# SCH_SAO-ctf-2024_2024-02-16.net
KiCad netlist of a schematic drawn in EasyEDA
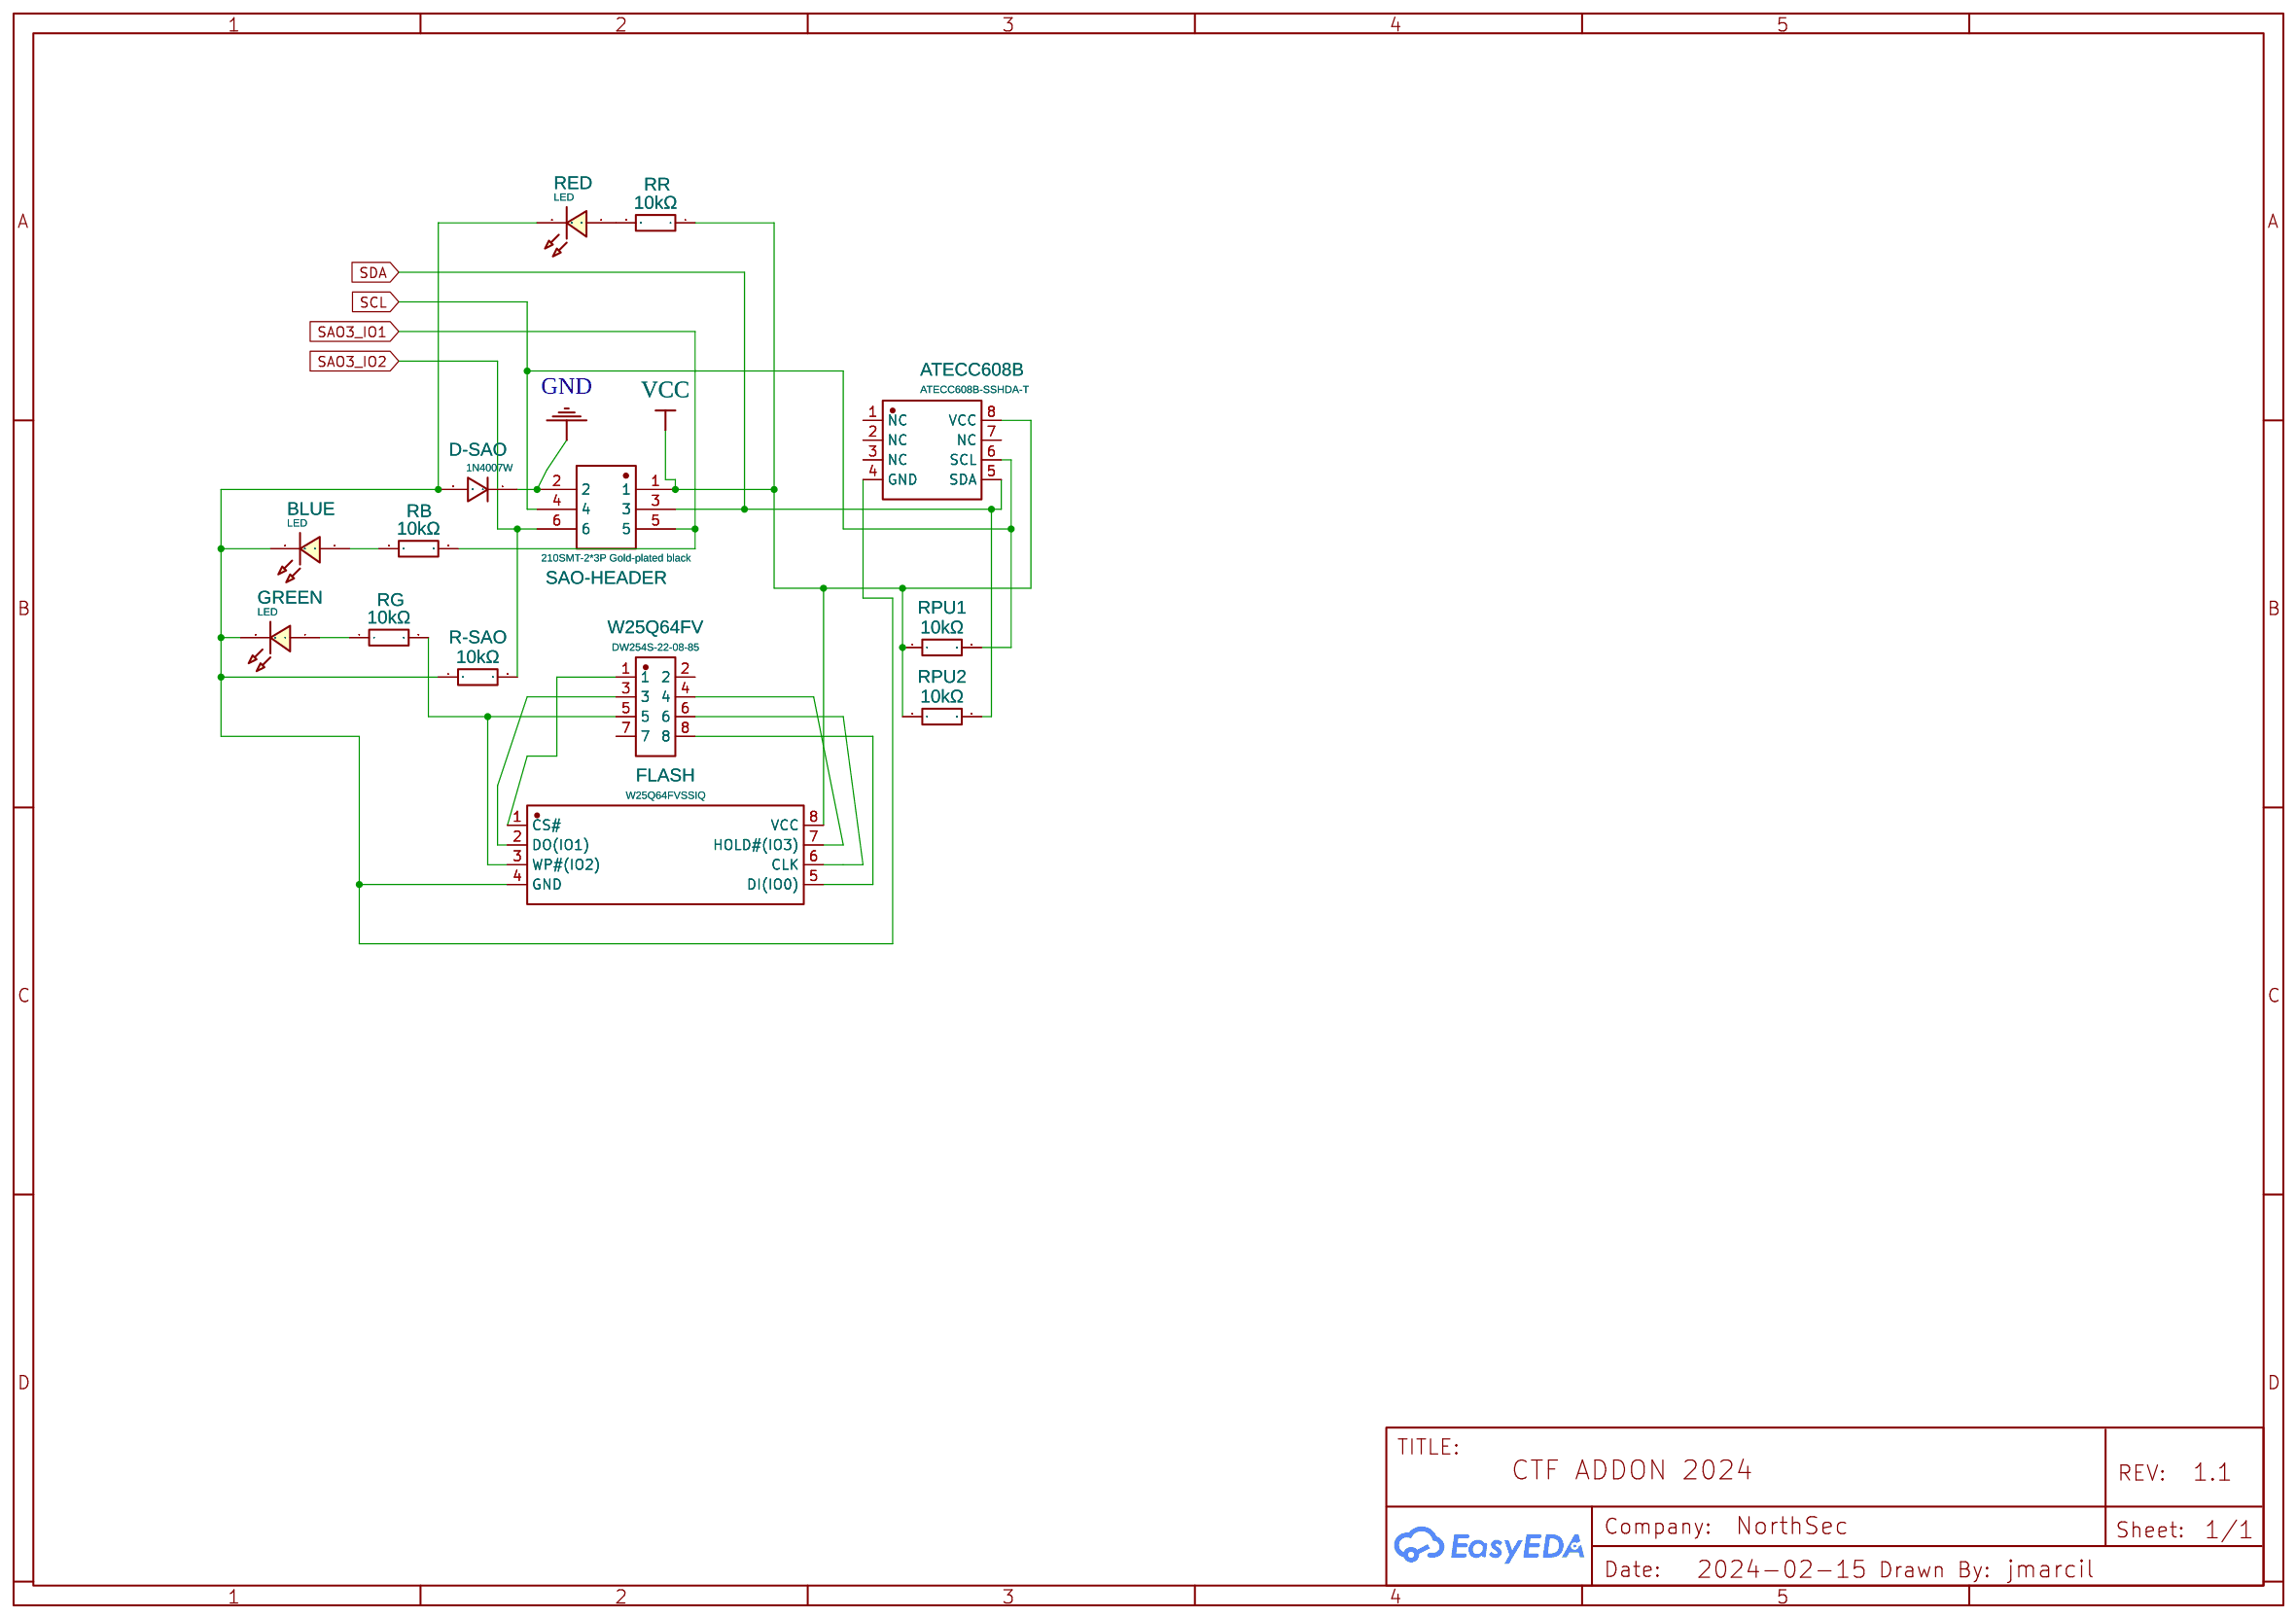
[diagram p0: schematic sheet]

(export (version "E")
  (design (tool "Eeschema 10.0.6"))
  (components
    (comp (ref "ATECC608B")
      (value "ATECC608B-SSHDA-T")
      (fields (field (name "Manufacturer") "MICROCHIP(美国微芯)"))
      (libsource (lib "") (part "ATECC608B-SSHDA-T"))
    )
    (comp (ref "BLUE")
      (value "LED")
      (fields
        (field (name "Manufacturer Part") "19-217/BHC-ZL1M2RY/3T")
        (field (name "Manufacturer") "EVERLIGHT(台湾亿光)")
      )
      (libsource (lib "") (part "LED-0603_B"))
    )
    (comp (ref "D-SAO")
      (value "1N4007W")
      (fields (field (name "Manufacturer") "BLUE ROCKET"))
      (libsource (lib "") (part "1N4007W"))
    )
    (comp (ref "FLASH")
      (value "W25Q64FVSSIQ")
      (fields (field (name "Manufacturer") "WINBOND(华邦)"))
      (libsource (lib "") (part "W25Q64FVSSIQ"))
    )
    (comp (ref "GREEN")
      (value "LED")
      (fields
        (field (name "Manufacturer Part") "19-217/GHC-YR1S2/3T")
        (field (name "Manufacturer") "EVERLIGHT(台湾亿光)")
      )
      (libsource (lib "") (part "LED-0603_G"))
    )
    (comp (ref "R-SAO")
      (value "10kΩ")
      (fields
        (field (name "Manufacturer Part") "1206W4F1002T5E")
        (field (name "Manufacturer") "UNI-ROYAL(厚声)")
      )
      (libsource (lib "") (part "1206W4F1002T5E"))
    )
    (comp (ref "RB")
      (value "10kΩ")
      (fields
        (field (name "Manufacturer Part") "1206W4F1002T5E")
        (field (name "Manufacturer") "UNI-ROYAL(厚声)")
      )
      (libsource (lib "") (part "1206W4F1002T5E_1"))
    )
    (comp (ref "RED")
      (value "LED")
      (fields
        (field (name "Manufacturer Part") "19-217/R6C-AL1M2VY/3T")
        (field (name "Manufacturer") "EVERLIGHT(台湾亿光)")
      )
      (libsource (lib "") (part "LED-0603_R"))
    )
    (comp (ref "RG")
      (value "10kΩ")
      (fields
        (field (name "Manufacturer Part") "1206W4F1002T5E")
        (field (name "Manufacturer") "UNI-ROYAL(厚声)")
      )
      (libsource (lib "") (part "1206W4F1002T5E_2"))
    )
    (comp (ref "RPU1")
      (value "10kΩ")
      (fields
        (field (name "Manufacturer Part") "1206W4F1002T5E")
        (field (name "Manufacturer") "UNI-ROYAL(厚声)")
      )
      (libsource (lib "") (part "1206W4F1002T5E_4"))
    )
    (comp (ref "RPU2")
      (value "10kΩ")
      (fields
        (field (name "Manufacturer Part") "1206W4F1002T5E")
        (field (name "Manufacturer") "UNI-ROYAL(厚声)")
      )
      (libsource (lib "") (part "1206W4F1002T5E_4"))
    )
    (comp (ref "RR")
      (value "10kΩ")
      (fields
        (field (name "Manufacturer Part") "1206W4F1002T5E")
        (field (name "Manufacturer") "UNI-ROYAL(厚声)")
      )
      (libsource (lib "") (part "1206W4F1002T5E_3"))
    )
    (comp (ref "SAO-HEADER")
      (value "210SMT-2*3P Gold-plated black")
      (fields (field (name "Manufacturer Part") "B-2100N06P-B111") (field (name "Manufacturer") "Ckmtw(灿科盟)"))
      (libsource (lib "") (part "210SMT-2*3P Gold-plated black"))
    )
    (comp (ref "W25Q64FV")
      (value "DW254S-22-08-85")
      (fields (field (name "Manufacturer") "DEALON(德艺隆)"))
      (libsource (lib "") (part "DW254S-22-08-85"))
    )
  )
  (nets
    (net (code "1") (name "GND") (class "Default")
      (node (ref "D-SAO") (pin "1") (pinfunction "1_1") (pintype "unspecified"))
      (node (ref "SAO-HEADER") (pin "2") (pinfunction "2_2") (pintype "unspecified"))
    )
    (net (code "2") (name "Net-(ATECC608B-GND)") (class "Default")
      (node (ref "ATECC608B") (pin "4") (pinfunction "GND_4") (pintype "unspecified"))
      (node (ref "BLUE") (pin "2") (pinfunction "2_2") (pintype "unspecified"))
      (node (ref "D-SAO") (pin "2") (pinfunction "2_2") (pintype "unspecified"))
      (node (ref "FLASH") (pin "4") (pinfunction "GND_4") (pintype "unspecified"))
      (node (ref "GREEN") (pin "2") (pinfunction "2_2") (pintype "unspecified"))
      (node (ref "R-SAO") (pin "1") (pinfunction "1_1") (pintype "input"))
      (node (ref "RED") (pin "2") (pinfunction "2_2") (pintype "unspecified"))
    )
    (net (code "3") (name "Net-(BLUE-Pad1)") (class "Default")
      (node (ref "BLUE") (pin "1") (pinfunction "1_1") (pintype "unspecified"))
      (node (ref "RB") (pin "1") (pinfunction "1_1") (pintype "input"))
    )
    (net (code "4") (name "Net-(FLASH-CLK)") (class "Default")
      (node (ref "FLASH") (pin "6") (pinfunction "CLK_6") (pintype "unspecified"))
      (node (ref "W25Q64FV") (pin "6") (pinfunction "6_6") (pintype "unspecified"))
    )
    (net (code "5") (name "Net-(FLASH-CS#)") (class "Default")
      (node (ref "FLASH") (pin "1") (pinfunction "CS#_1") (pintype "unspecified"))
      (node (ref "W25Q64FV") (pin "1") (pinfunction "1_1") (pintype "unspecified"))
    )
    (net (code "6") (name "Net-(FLASH-DI(IO0))") (class "Default")
      (node (ref "FLASH") (pin "5") (pinfunction "DI(IO0)_5") (pintype "unspecified"))
      (node (ref "W25Q64FV") (pin "8") (pinfunction "8_8") (pintype "unspecified"))
    )
    (net (code "7") (name "Net-(FLASH-DO(IO1))") (class "Default")
      (node (ref "FLASH") (pin "2") (pinfunction "DO(IO1)_2") (pintype "unspecified"))
      (node (ref "W25Q64FV") (pin "3") (pinfunction "3_3") (pintype "unspecified"))
    )
    (net (code "8") (name "Net-(FLASH-HOLD#(IO3))") (class "Default")
      (node (ref "FLASH") (pin "7") (pinfunction "HOLD#(IO3)_7") (pintype "unspecified"))
      (node (ref "W25Q64FV") (pin "4") (pinfunction "4_4") (pintype "unspecified"))
    )
    (net (code "9") (name "Net-(FLASH-WP#(IO2))") (class "Default")
      (node (ref "FLASH") (pin "3") (pinfunction "WP#(IO2)_3") (pintype "unspecified"))
      (node (ref "RG") (pin "2") (pinfunction "2_2") (pintype "input"))
      (node (ref "W25Q64FV") (pin "5") (pinfunction "5_5") (pintype "unspecified"))
    )
    (net (code "10") (name "Net-(GREEN-Pad1)") (class "Default")
      (node (ref "GREEN") (pin "1") (pinfunction "1_1") (pintype "unspecified"))
      (node (ref "RG") (pin "1") (pinfunction "1_1") (pintype "input"))
    )
    (net (code "11") (name "Net-(RED-Pad1)") (class "Default")
      (node (ref "RED") (pin "1") (pinfunction "1_1") (pintype "unspecified"))
      (node (ref "RR") (pin "2") (pinfunction "2_2") (pintype "input"))
    )
    (net (code "12") (name "SAO3_IO1") (class "Default")
      (node (ref "RB") (pin "2") (pinfunction "2_2") (pintype "input"))
      (node (ref "SAO-HEADER") (pin "5") (pinfunction "5_5") (pintype "unspecified"))
    )
    (net (code "13") (name "SAO3_IO2") (class "Default")
      (node (ref "R-SAO") (pin "2") (pinfunction "2_2") (pintype "input"))
      (node (ref "SAO-HEADER") (pin "6") (pinfunction "6_6") (pintype "unspecified"))
    )
    (net (code "14") (name "SCL") (class "Default")
      (node (ref "ATECC608B") (pin "6") (pinfunction "SCL_6") (pintype "unspecified"))
      (node (ref "RPU1") (pin "2") (pinfunction "2_2") (pintype "input"))
      (node (ref "SAO-HEADER") (pin "4") (pinfunction "4_4") (pintype "unspecified"))
    )
    (net (code "15") (name "SDA") (class "Default")
      (node (ref "ATECC608B") (pin "5") (pinfunction "SDA_5") (pintype "unspecified"))
      (node (ref "RPU2") (pin "2") (pinfunction "2_2") (pintype "input"))
      (node (ref "SAO-HEADER") (pin "3") (pinfunction "3_3") (pintype "unspecified"))
    )
    (net (code "16") (name "VCC") (class "Default")
      (node (ref "ATECC608B") (pin "8") (pinfunction "VCC_8") (pintype "unspecified"))
      (node (ref "FLASH") (pin "8") (pinfunction "VCC_8") (pintype "unspecified"))
      (node (ref "RPU1") (pin "1") (pinfunction "1_1") (pintype "input"))
      (node (ref "RPU2") (pin "1") (pinfunction "1_1") (pintype "input"))
      (node (ref "RR") (pin "1") (pinfunction "1_1") (pintype "input"))
      (node (ref "SAO-HEADER") (pin "1") (pinfunction "1_1") (pintype "unspecified"))
    )
    (net (code "17") (name "unconnected-(ATECC608B-NC-Pad1)") (class "Default")
      (node (ref "ATECC608B") (pin "1") (pinfunction "NC_1") (pintype "unspecified"))
    )
    (net (code "18") (name "unconnected-(ATECC608B-NC-Pad2)") (class "Default")
      (node (ref "ATECC608B") (pin "2") (pinfunction "NC_2") (pintype "unspecified"))
    )
    (net (code "19") (name "unconnected-(ATECC608B-NC-Pad3)") (class "Default")
      (node (ref "ATECC608B") (pin "3") (pinfunction "NC_3") (pintype "unspecified"))
    )
    (net (code "20") (name "unconnected-(ATECC608B-NC-Pad7)") (class "Default")
      (node (ref "ATECC608B") (pin "7") (pinfunction "NC_7") (pintype "unspecified"))
    )
    (net (code "21") (name "unconnected-(W25Q64FV-Pad2)") (class "Default")
      (node (ref "W25Q64FV") (pin "2") (pinfunction "2_2") (pintype "unspecified"))
    )
    (net (code "22") (name "unconnected-(W25Q64FV-Pad7)") (class "Default")
      (node (ref "W25Q64FV") (pin "7") (pinfunction "7_7") (pintype "unspecified"))
    )
  )
)
